# spi_eeprom.net
KiCad netlist of a schematic drawn in EAGLE
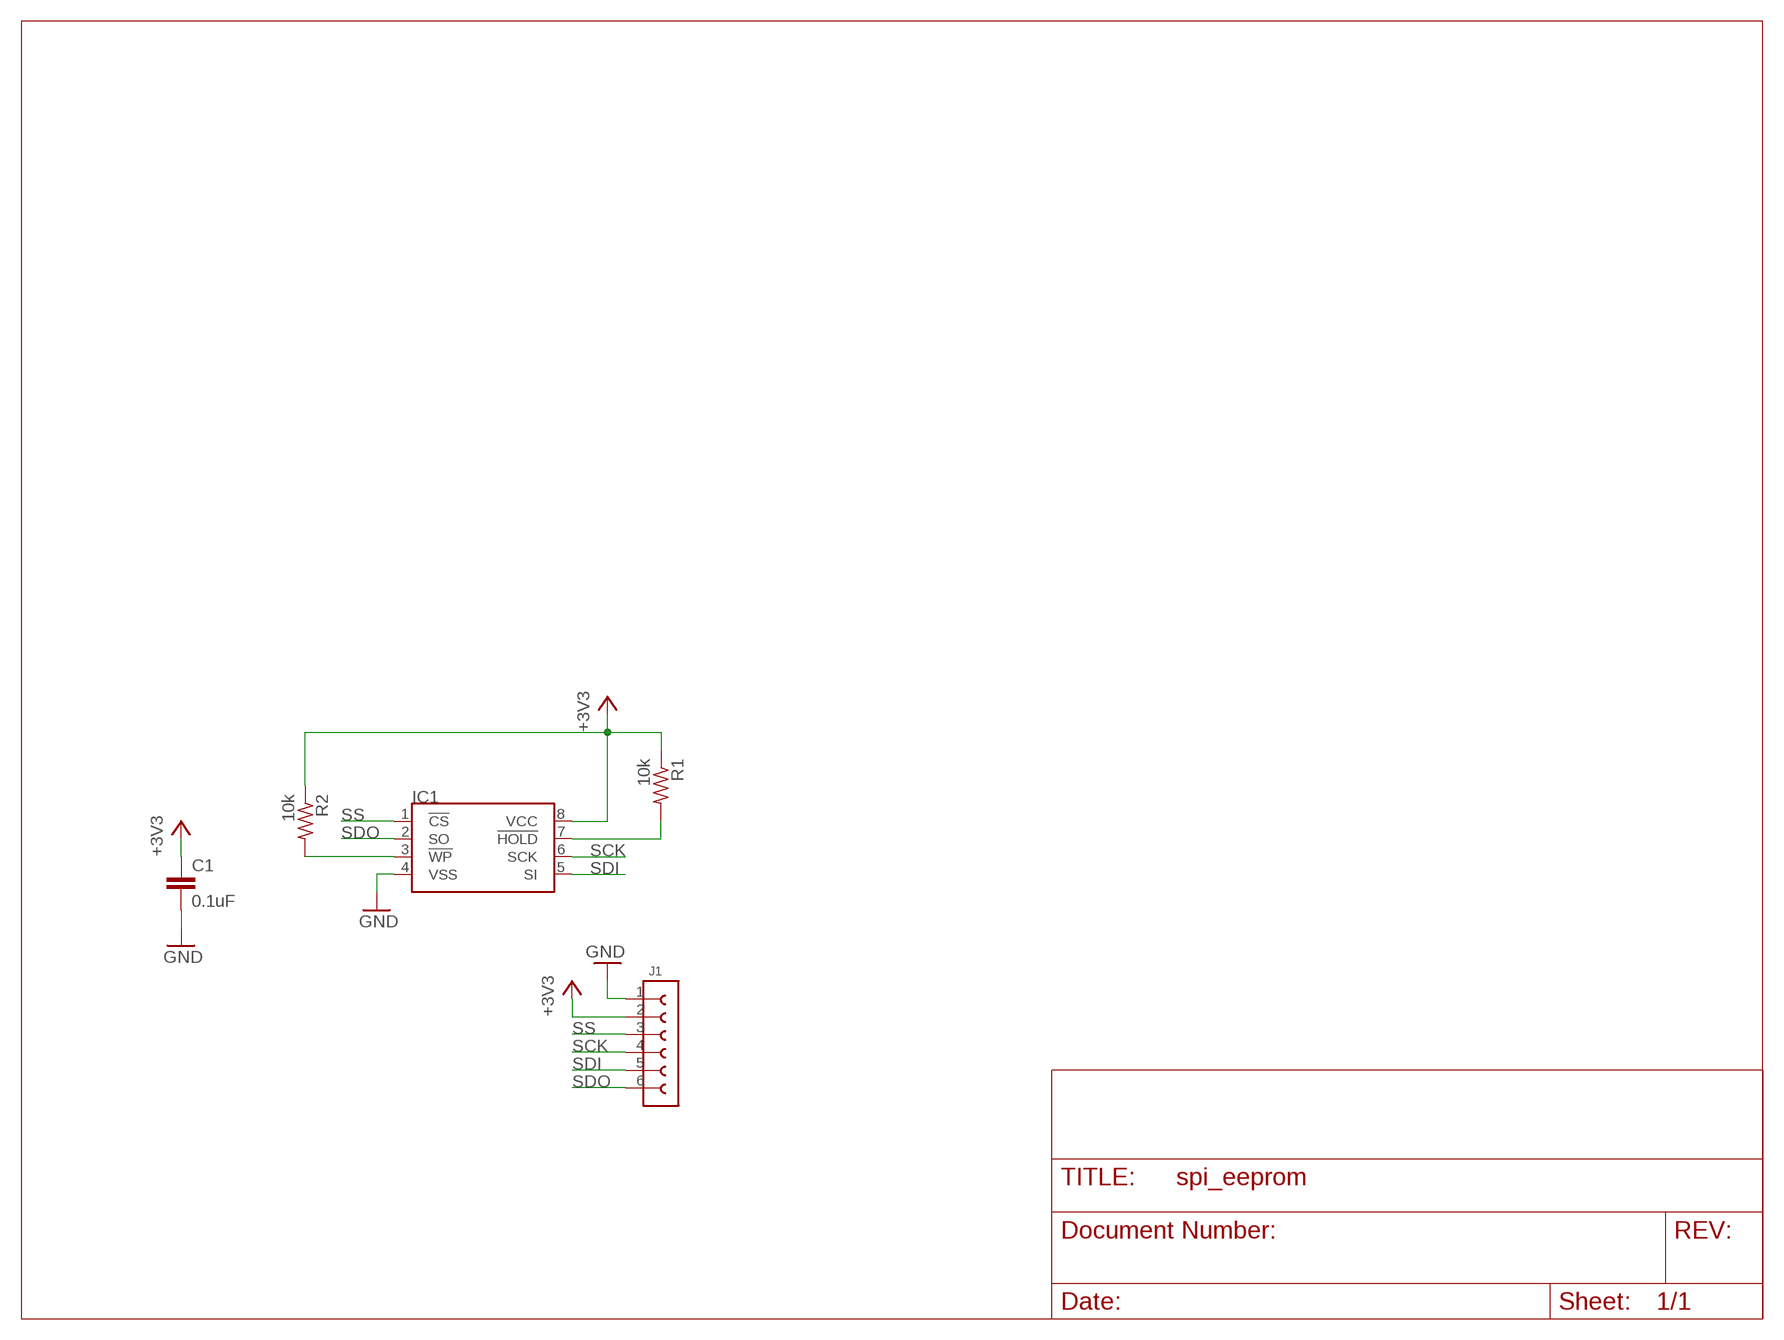
[diagram p0: schematic, sheet 1]

(export (version "E")
  (design (tool "Eeschema 10.0.6"))
  (components
    (comp (ref "C1")
      (value "0.1uF")
      (footprint "eagle-import:CAPC0603")
      (fields (field (name "MANUFACTURER") "KEMET"))
      (libsource (lib "eagle-import") (part "C?CVAC0603104Z3"))
    )
    (comp (ref "IC1")
      (value "25LC320A-I/SN")
      (footprint "eagle-import:SOIC127P600X175-8N")
      (libsource (lib "eagle-import") (part "25320A-I/?SNLC"))
    )
    (comp (ref "J1")
      (value "61300611121")
      (footprint "eagle-import:PHSP254P1524X254X1154-6S")
      (fields (field (name "MANUFACTURER") "WURTH") (field (name "EAGLEUP") "PHSP254P1524X254X1154-6S"))
      (libsource (lib "eagle-import") (part "6130061?1121"))
    )
    (comp (ref "R1")
      (value "10k")
      (footprint "eagle-import:RESC0603")
      (libsource (lib "eagle-import") (part "CRG?0603F10K10"))
    )
    (comp (ref "R2")
      (value "10k")
      (footprint "eagle-import:RESC0603")
      (libsource (lib "eagle-import") (part "CRG?0603F10K10"))
    )
  )
  (nets
    (net (code "1") (name "+3V3") (class "Default")
      (node (ref "C1") (pin "1") (pinfunction "1_1") (pintype "passive"))
      (node (ref "IC1") (pin "8") (pinfunction "VCC_8") (pintype "power_in"))
      (node (ref "J1") (pin "2") (pinfunction "2_2") (pintype "passive"))
      (node (ref "R1") (pin "P$1") (pinfunction "1_P$1") (pintype "passive"))
      (node (ref "R2") (pin "P$1") (pinfunction "1_P$1") (pintype "passive"))
    )
    (net (code "2") (name "/SCK") (class "Default")
      (node (ref "IC1") (pin "6") (pinfunction "SCK_6") (pintype "bidirectional"))
      (node (ref "J1") (pin "4") (pinfunction "4_4") (pintype "passive"))
    )
    (net (code "3") (name "/SDI") (class "Default")
      (node (ref "IC1") (pin "5") (pinfunction "SI_5") (pintype "bidirectional"))
      (node (ref "J1") (pin "5") (pinfunction "5_5") (pintype "passive"))
    )
    (net (code "4") (name "/SDO") (class "Default")
      (node (ref "IC1") (pin "2") (pinfunction "SO_2") (pintype "bidirectional"))
      (node (ref "J1") (pin "6") (pinfunction "6_6") (pintype "passive"))
    )
    (net (code "5") (name "/SS") (class "Default")
      (node (ref "IC1") (pin "1") (pinfunction "~{CS}_1") (pintype "bidirectional"))
      (node (ref "J1") (pin "3") (pinfunction "3_3") (pintype "passive"))
    )
    (net (code "6") (name "GND") (class "Default")
      (node (ref "C1") (pin "2") (pinfunction "2_2") (pintype "passive"))
      (node (ref "IC1") (pin "4") (pinfunction "VSS_4") (pintype "power_in"))
      (node (ref "J1") (pin "1") (pinfunction "1_1") (pintype "passive"))
    )
    (net (code "7") (name "Net-(IC1-~{HOLD})") (class "Default")
      (node (ref "IC1") (pin "7") (pinfunction "~{HOLD}_7") (pintype "bidirectional"))
      (node (ref "R1") (pin "P$2") (pinfunction "2_P$2") (pintype "passive"))
    )
    (net (code "8") (name "Net-(IC1-~{WP})") (class "Default")
      (node (ref "IC1") (pin "3") (pinfunction "~{WP}_3") (pintype "bidirectional"))
      (node (ref "R2") (pin "P$2") (pinfunction "2_P$2") (pintype "passive"))
    )
  )
)
